# Dev_lcd_supply.net
KiCad netlist of a schematic drawn in EAGLE
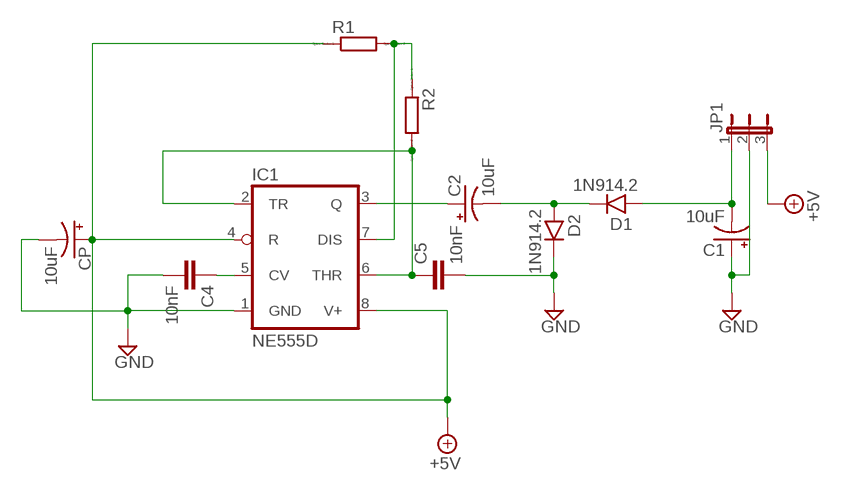
[diagram p0: schematic, sheet 1]

(export (version "E")
  (design (tool "Eeschema 10.0.6"))
  (components
    (comp (ref "C1")
      (value "10uF")
      (footprint "eagle-import:EIA3216")
      (libsource (lib "eagle-import") (part "10UF-TANT"))
    )
    (comp (ref "C2")
      (value "10uF")
      (footprint "eagle-import:EIA3216")
      (libsource (lib "eagle-import") (part "10UF-TANT"))
    )
    (comp (ref "C4")
      (value "10nF")
      (footprint "eagle-import:0402-CAP")
      (libsource (lib "eagle-import") (part "10NF-CER"))
    )
    (comp (ref "C5")
      (value "10nF")
      (footprint "eagle-import:0402-CAP")
      (libsource (lib "eagle-import") (part "10NF-CER"))
    )
    (comp (ref "CP")
      (value "10uF")
      (footprint "eagle-import:EIA3216")
      (libsource (lib "eagle-import") (part "10UF-TANT"))
    )
    (comp (ref "D1")
      (value "1N914.2")
      (footprint "eagle-import:DO35-2")
      (libsource (lib "eagle-import") (part "1N914.2"))
    )
    (comp (ref "D2")
      (value "1N914.2")
      (footprint "eagle-import:DO35-2")
      (libsource (lib "eagle-import") (part "1N914.2"))
    )
    (comp (ref "IC1")
      (value "NE555D")
      (footprint "eagle-import:SO08")
      (libsource (lib "eagle-import") (part "555DNE"))
    )
    (comp (ref "JP1")
      (value "JP2E")
      (footprint "eagle-import:JP2")
      (libsource (lib "eagle-import") (part "JP2E"))
    )
    (comp (ref "R1")
      (value "RR0603")
      (footprint "eagle-import:R0603")
      (libsource (lib "eagle-import") (part "RR0603"))
    )
    (comp (ref "R2")
      (value "RR0603")
      (footprint "eagle-import:R0603")
      (libsource (lib "eagle-import") (part "RR0603"))
    )
  )
  (nets
    (net (code "1") (name "+5V") (class "Default")
      (node (ref "CP") (pin "A") (pinfunction "+_A") (pintype "passive"))
      (node (ref "IC1") (pin "4") (pinfunction "R_4") (pintype "input"))
      (node (ref "IC1") (pin "8") (pinfunction "V+_8") (pintype "power_in"))
      (node (ref "JP1") (pin "3") (pinfunction "3_3") (pintype "passive"))
      (node (ref "R1") (pin "1") (pinfunction "1_1") (pintype "passive"))
    )
    (net (code "2") (name "GND") (class "Default")
      (node (ref "C1") (pin "A") (pinfunction "+_A") (pintype "passive"))
      (node (ref "C4") (pin "2") (pinfunction "2_2") (pintype "passive"))
      (node (ref "C5") (pin "2") (pinfunction "2_2") (pintype "passive"))
      (node (ref "CP") (pin "C") (pinfunction "-_C") (pintype "passive"))
      (node (ref "D2") (pin "C") (pinfunction "C_C") (pintype "passive"))
      (node (ref "IC1") (pin "1") (pinfunction "GND_1") (pintype "power_in"))
      (node (ref "JP1") (pin "2") (pinfunction "2_2") (pintype "passive"))
    )
    (net (code "3") (name "Net-(C1--)") (class "Default")
      (node (ref "C1") (pin "C") (pinfunction "-_C") (pintype "passive"))
      (node (ref "D1") (pin "A") (pinfunction "A_A") (pintype "passive"))
      (node (ref "JP1") (pin "1") (pinfunction "1_1") (pintype "passive"))
    )
    (net (code "4") (name "Net-(C2-+)") (class "Default")
      (node (ref "C2") (pin "A") (pinfunction "+_A") (pintype "passive"))
      (node (ref "IC1") (pin "3") (pinfunction "Q_3") (pintype "output"))
    )
    (net (code "5") (name "Net-(C2--)") (class "Default")
      (node (ref "C2") (pin "C") (pinfunction "-_C") (pintype "passive"))
      (node (ref "D1") (pin "C") (pinfunction "C_C") (pintype "passive"))
      (node (ref "D2") (pin "A") (pinfunction "A_A") (pintype "passive"))
    )
    (net (code "6") (name "Net-(IC1-CV)") (class "Default")
      (node (ref "C4") (pin "1") (pinfunction "1_1") (pintype "passive"))
      (node (ref "IC1") (pin "5") (pinfunction "CV_5") (pintype "input"))
    )
    (net (code "7") (name "Net-(IC1-DIS)") (class "Default")
      (node (ref "IC1") (pin "7") (pinfunction "DIS_7") (pintype "input"))
      (node (ref "R1") (pin "2") (pinfunction "2_2") (pintype "passive"))
      (node (ref "R2") (pin "1") (pinfunction "1_1") (pintype "passive"))
    )
    (net (code "8") (name "Net-(IC1-THR)") (class "Default")
      (node (ref "C5") (pin "1") (pinfunction "1_1") (pintype "passive"))
      (node (ref "IC1") (pin "2") (pinfunction "TR_2") (pintype "input"))
      (node (ref "IC1") (pin "6") (pinfunction "THR_6") (pintype "input"))
      (node (ref "R2") (pin "2") (pinfunction "2_2") (pintype "passive"))
    )
  )
)
